# Sensor_Schematic.net
KiCad netlist of a schematic drawn in Altium Designer
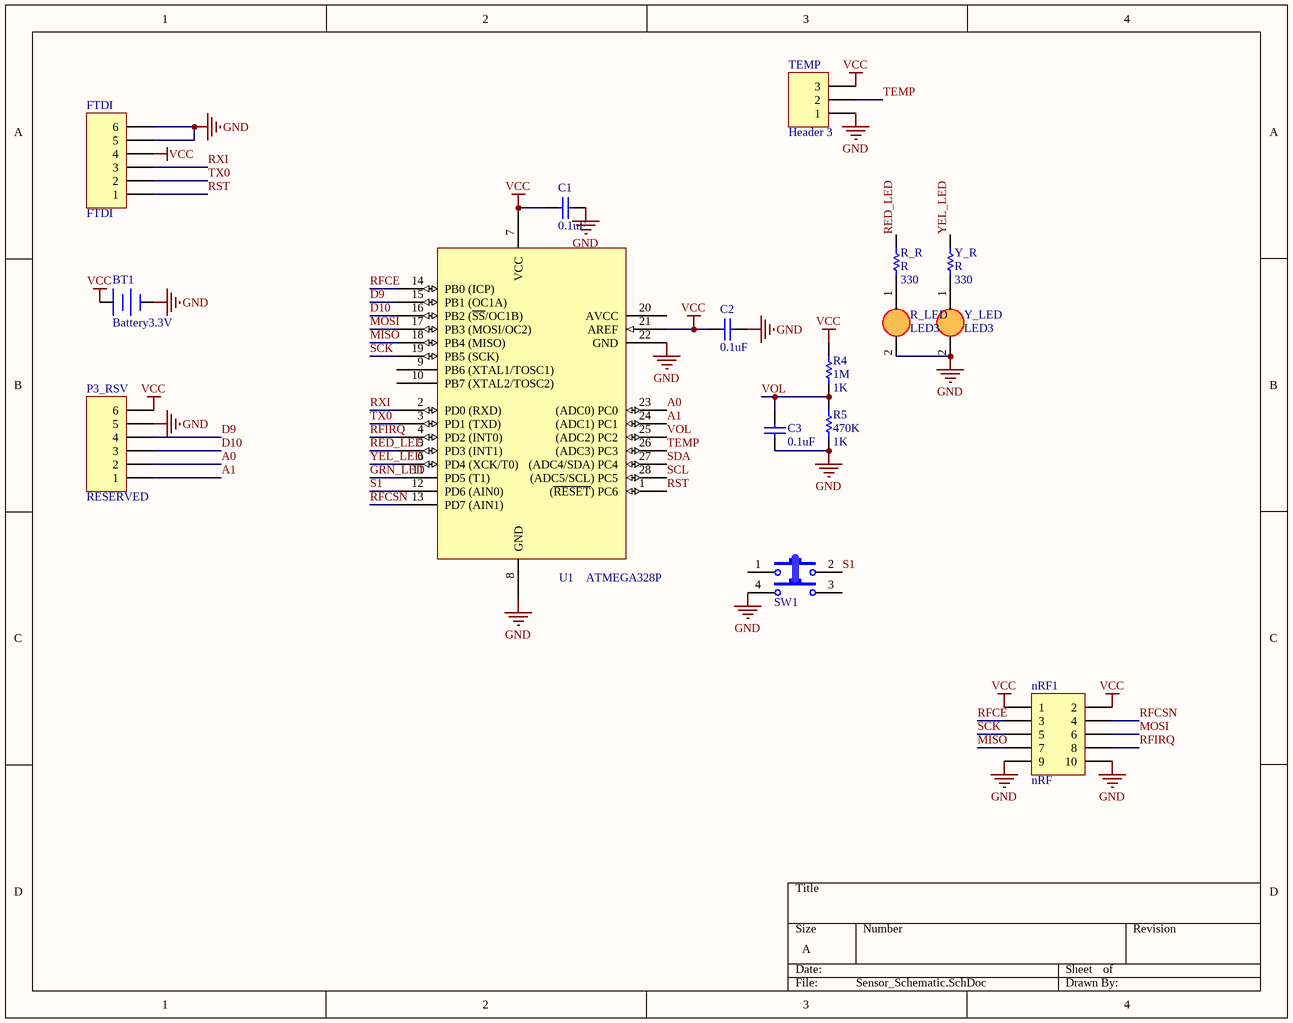
[diagram p0: Sensor_Schematic.SchDoc]

(export (version "E")
  (design (tool "Eeschema 10.0.6"))
  (components
    (comp (ref "BT1")
      (value "Battery3.3V")
      (footprint "CR2032 Holder")
      (description "Multicell Battery")
      (fields (field (name "PUBLISHER") "Altium Limited"))
      (libsource (lib "Arduino4Alitum_Library") (part "Battery3.3V"))
    )
    (comp (ref "C1")
      (value "0.1uF")
      (footprint "Tu-pico")
      (description "Capacitor")
      (fields (field (name "Comment") "Capacitor Ceramic") (field (name "PUBLISHER") "Altium Limited"))
      (libsource (lib "Arduino4Alitum_Library") (part "CapCeramic"))
    )
    (comp (ref "C2")
      (value "0.1uF")
      (footprint "Tu-pico")
      (description "Capacitor")
      (fields (field (name "Comment") "Capacitor Ceramic") (field (name "PUBLISHER") "Altium Limited"))
      (libsource (lib "Arduino4Alitum_Library") (part "CapCeramic"))
    )
    (comp (ref "C3")
      (value "0.1uF")
      (footprint "Tu-pico")
      (description "Capacitor")
      (fields (field (name "Comment") "Capacitor Ceramic") (field (name "PUBLISHER") "Altium Limited"))
      (libsource (lib "Arduino4Alitum_Library") (part "CapCeramic"))
    )
    (comp (ref "FTDI")
      (value "FTDI")
      (footprint "HDR1X6")
      (description "Header, 6-Pin")
      (fields (field (name "PUBLISHER") "Altium Limited"))
      (libsource (lib "Miscellaneous Connectors") (part "Header 6"))
    )
    (comp (ref "nRF1")
      (value "nRF")
      (footprint "HDR2X5")
      (description "Header, 5-Pin, Dual row")
      (fields (field (name "PUBLISHER") "Altium Limited"))
      (libsource (lib "Miscellaneous Connectors") (part "Header 5X2"))
    )
    (comp (ref "P3_RSV")
      (value "RESERVED")
      (footprint "HDR1X6")
      (description "Header, 6-Pin")
      (fields (field (name "PUBLISHER") "Altium Limited"))
      (libsource (lib "Miscellaneous Connectors") (part "Header 6"))
    )
    (comp (ref "R4")
      (value "1M")
      (footprint "AXIAL-0.3")
      (description "Resistor")
      (fields (field (name "ALTIUM_VALUE") "1K") (field (name "PUBLISHER") "Altium Limited"))
      (libsource (lib "Miscellaneous Devices") (part "Res1"))
    )
    (comp (ref "R5")
      (value "470K")
      (footprint "AXIAL-0.3")
      (description "Resistor")
      (fields (field (name "ALTIUM_VALUE") "1K") (field (name "PUBLISHER") "Altium Limited"))
      (libsource (lib "Miscellaneous Devices") (part "Res1"))
    )
    (comp (ref "R_LED")
      (value "LED3")
      (footprint "LED3mm")
      (description "LED 3mm")
      (libsource (lib "Arduino4Alitum_Library") (part "LED 3mm"))
    )
    (comp (ref "R_R")
      (value "R")
      (footprint "AXIAL-0.3")
      (description "Resistor")
      (fields (field (name "ALTIUM_VALUE") "330") (field (name "PUBLISHER") "Altium Limited"))
      (libsource (lib "Miscellaneous Devices") (part "Res1"))
    )
    (comp (ref "SW1")
      (value "SW-4P-B")
      (footprint "SW-4P-B")
      (description "Switch Big 4 Pin")
      (fields (field (name "PUBLISHER") "Altium Limited"))
      (libsource (lib "NBBLib 14-03-2012") (part "SW-4PIN-BIG"))
    )
    (comp (ref "TEMP")
      (value "Header 3")
      (footprint "HDR1X3")
      (description "Header, 3-Pin")
      (fields (field (name "PUBLISHER") "Altium Limited"))
      (libsource (lib "Miscellaneous Connectors") (part "Header 3"))
    )
    (comp (ref "U1")
      (value "ATMEGA328P")
      (footprint "AVR_DIP28P")
      (description "Atmel Microcontroller - Library created by carel..  <www.mpfreezone.com>")
      (libsource (lib "Arduino4Alitum_Library") (part "ATMEGA8_DIP28"))
    )
    (comp (ref "Y_LED")
      (value "LED3")
      (footprint "LED3mm")
      (description "LED 3mm")
      (libsource (lib "Arduino4Alitum_Library") (part "LED 3mm"))
    )
    (comp (ref "Y_R")
      (value "R")
      (footprint "AXIAL-0.3")
      (description "Resistor")
      (fields (field (name "ALTIUM_VALUE") "330") (field (name "PUBLISHER") "Altium Limited"))
      (libsource (lib "Miscellaneous Devices") (part "Res1"))
    )
  )
  (nets
    (net (code "1") (name "/A0") (class "Default")
      (node (ref "P3_RSV") (pin "2") (pinfunction "2_2") (pintype "passive"))
      (node (ref "U1") (pin "23") (pinfunction "(ADC0)_PC0_23") (pintype "bidirectional"))
    )
    (net (code "2") (name "/A1") (class "Default")
      (node (ref "P3_RSV") (pin "1") (pinfunction "1_1") (pintype "passive"))
      (node (ref "U1") (pin "24") (pinfunction "(ADC1)_PC1_24") (pintype "bidirectional"))
    )
    (net (code "3") (name "/D9") (class "Default")
      (node (ref "P3_RSV") (pin "4") (pinfunction "4_4") (pintype "passive"))
      (node (ref "U1") (pin "15") (pinfunction "PB1_(OC1A)_15") (pintype "bidirectional"))
    )
    (net (code "4") (name "/D10") (class "Default")
      (node (ref "P3_RSV") (pin "3") (pinfunction "3_3") (pintype "passive"))
      (node (ref "U1") (pin "16") (pinfunction "PB2_(~{SS}/OC1B)_16") (pintype "bidirectional"))
    )
    (net (code "5") (name "/GRN_LED") (class "Default")
      (node (ref "U1") (pin "11") (pinfunction "PD5_(T1)_11") (pintype "passive"))
    )
    (net (code "6") (name "/MISO") (class "Default")
      (node (ref "U1") (pin "18") (pinfunction "PB4_(MISO)_18") (pintype "bidirectional"))
      (node (ref "nRF1") (pin "7") (pinfunction "7_7") (pintype "passive"))
    )
    (net (code "7") (name "/MOSI") (class "Default")
      (node (ref "U1") (pin "17") (pinfunction "PB3_(MOSI/OC2)_17") (pintype "bidirectional"))
      (node (ref "nRF1") (pin "6") (pinfunction "6_6") (pintype "passive"))
    )
    (net (code "8") (name "/RED_LED") (class "Default")
      (node (ref "R_R") (pin "2") (pinfunction "2_2") (pintype "passive"))
      (node (ref "U1") (pin "5") (pinfunction "PD3_(INT1)_5") (pintype "bidirectional"))
    )
    (net (code "9") (name "/RFCE") (class "Default")
      (node (ref "U1") (pin "14") (pinfunction "PB0_(ICP)_14") (pintype "bidirectional"))
      (node (ref "nRF1") (pin "3") (pinfunction "3_3") (pintype "passive"))
    )
    (net (code "10") (name "/RFCSN") (class "Default")
      (node (ref "U1") (pin "13") (pinfunction "PD7_(AIN1)_13") (pintype "passive"))
      (node (ref "nRF1") (pin "4") (pinfunction "4_4") (pintype "passive"))
    )
    (net (code "11") (name "/RFIRQ") (class "Default")
      (node (ref "U1") (pin "4") (pinfunction "PD2_(INT0)_4") (pintype "bidirectional"))
      (node (ref "nRF1") (pin "8") (pinfunction "8_8") (pintype "passive"))
    )
    (net (code "12") (name "/RST") (class "Default")
      (node (ref "FTDI") (pin "1") (pinfunction "1_1") (pintype "passive"))
      (node (ref "U1") (pin "1") (pinfunction "(~{RESET})_PC6_1") (pintype "bidirectional"))
    )
    (net (code "13") (name "/RXI") (class "Default")
      (node (ref "FTDI") (pin "3") (pinfunction "3_3") (pintype "passive"))
      (node (ref "U1") (pin "2") (pinfunction "PD0_(RXD)_2") (pintype "bidirectional"))
    )
    (net (code "14") (name "/S1") (class "Default")
      (node (ref "SW1") (pin "2") (pinfunction "2_2") (pintype "passive"))
      (node (ref "U1") (pin "12") (pinfunction "PD6_(AIN0)_12") (pintype "passive"))
    )
    (net (code "15") (name "/SCK") (class "Default")
      (node (ref "U1") (pin "19") (pinfunction "PB5_(SCK)_19") (pintype "bidirectional"))
      (node (ref "nRF1") (pin "5") (pinfunction "5_5") (pintype "passive"))
    )
    (net (code "16") (name "/SCL") (class "Default")
      (node (ref "U1") (pin "28") (pinfunction "(ADC5/SCL)_PC5_28") (pintype "bidirectional"))
    )
    (net (code "17") (name "/SDA") (class "Default")
      (node (ref "U1") (pin "27") (pinfunction "(ADC4/SDA)_PC4_27") (pintype "bidirectional"))
    )
    (net (code "18") (name "/TEMP") (class "Default")
      (node (ref "TEMP") (pin "2") (pinfunction "2_2") (pintype "passive"))
      (node (ref "U1") (pin "26") (pinfunction "(ADC3)_PC3_26") (pintype "bidirectional"))
    )
    (net (code "19") (name "/TX0") (class "Default")
      (node (ref "FTDI") (pin "2") (pinfunction "2_2") (pintype "passive"))
      (node (ref "U1") (pin "3") (pinfunction "PD1_(TXD)_3") (pintype "bidirectional"))
    )
    (net (code "20") (name "/VOL") (class "Default")
      (node (ref "C3") (pin "2") (pinfunction "2_2") (pintype "passive"))
      (node (ref "R4") (pin "1") (pinfunction "1_1") (pintype "passive"))
      (node (ref "R5") (pin "2") (pinfunction "2_2") (pintype "passive"))
      (node (ref "U1") (pin "25") (pinfunction "(ADC2)_PC2_25") (pintype "bidirectional"))
    )
    (net (code "21") (name "/YEL_LED") (class "Default")
      (node (ref "U1") (pin "6") (pinfunction "PD4_(XCK/T0)_6") (pintype "bidirectional"))
      (node (ref "Y_R") (pin "2") (pinfunction "2_2") (pintype "passive"))
    )
    (net (code "22") (name "GND") (class "Default")
      (node (ref "BT1") (pin "2") (pinfunction "-_2") (pintype "passive"))
      (node (ref "C1") (pin "2") (pinfunction "2_2") (pintype "passive"))
      (node (ref "C2") (pin "2") (pinfunction "2_2") (pintype "passive"))
      (node (ref "C3") (pin "1") (pinfunction "1_1") (pintype "passive"))
      (node (ref "FTDI") (pin "5") (pinfunction "5_5") (pintype "passive"))
      (node (ref "FTDI") (pin "6") (pinfunction "6_6") (pintype "passive"))
      (node (ref "P3_RSV") (pin "5") (pinfunction "5_5") (pintype "passive"))
      (node (ref "R5") (pin "1") (pinfunction "1_1") (pintype "passive"))
      (node (ref "R_LED") (pin "2") (pinfunction "K_2") (pintype "passive"))
      (node (ref "SW1") (pin "4") (pinfunction "4_4") (pintype "passive"))
      (node (ref "TEMP") (pin "1") (pinfunction "1_1") (pintype "passive"))
      (node (ref "U1") (pin "22") (pinfunction "GND_22") (pintype "passive"))
      (node (ref "U1") (pin "8") (pinfunction "GND_8") (pintype "passive"))
      (node (ref "Y_LED") (pin "2") (pinfunction "K_2") (pintype "passive"))
      (node (ref "nRF1") (pin "10") (pinfunction "10_10") (pintype "passive"))
      (node (ref "nRF1") (pin "9") (pinfunction "9_9") (pintype "passive"))
    )
    (net (code "23") (name "Net-(R_LED-A)") (class "Default")
      (node (ref "R_LED") (pin "1") (pinfunction "A_1") (pintype "passive"))
      (node (ref "R_R") (pin "1") (pinfunction "1_1") (pintype "passive"))
    )
    (net (code "24") (name "Net-(Y_LED-A)") (class "Default")
      (node (ref "Y_LED") (pin "1") (pinfunction "A_1") (pintype "passive"))
      (node (ref "Y_R") (pin "1") (pinfunction "1_1") (pintype "passive"))
    )
    (net (code "25") (name "VCC") (class "Default")
      (node (ref "BT1") (pin "1") (pinfunction "+_1") (pintype "passive"))
      (node (ref "C1") (pin "1") (pinfunction "1_1") (pintype "passive"))
      (node (ref "C2") (pin "1") (pinfunction "1_1") (pintype "passive"))
      (node (ref "FTDI") (pin "4") (pinfunction "4_4") (pintype "passive"))
      (node (ref "P3_RSV") (pin "6") (pinfunction "6_6") (pintype "passive"))
      (node (ref "R4") (pin "2") (pinfunction "2_2") (pintype "passive"))
      (node (ref "TEMP") (pin "3") (pinfunction "3_3") (pintype "passive"))
      (node (ref "U1") (pin "21") (pinfunction "AREF_21") (pintype "input"))
      (node (ref "U1") (pin "7") (pinfunction "VCC_7") (pintype "passive"))
      (node (ref "nRF1") (pin "1") (pinfunction "1_1") (pintype "passive"))
      (node (ref "nRF1") (pin "2") (pinfunction "2_2") (pintype "passive"))
    )
    (net (code "26") (name "unconnected-(SW1-Pad1)") (class "Default")
      (node (ref "SW1") (pin "1") (pinfunction "1_1") (pintype "passive"))
    )
    (net (code "27") (name "unconnected-(SW1-Pad3)") (class "Default")
      (node (ref "SW1") (pin "3") (pinfunction "3_3") (pintype "passive"))
    )
    (net (code "28") (name "unconnected-(U1-AVCC-Pad20)") (class "Default")
      (node (ref "U1") (pin "20") (pinfunction "AVCC_20") (pintype "passive"))
    )
    (net (code "29") (name "unconnected-(U1-PB6_(XTAL1{slash}TOSC1)-Pad9)") (class "Default")
      (node (ref "U1") (pin "9") (pinfunction "PB6_(XTAL1/TOSC1)_9") (pintype "passive"))
    )
    (net (code "30") (name "unconnected-(U1-PB7_(XTAL2{slash}TOSC2)-Pad10)") (class "Default")
      (node (ref "U1") (pin "10") (pinfunction "PB7_(XTAL2/TOSC2)_10") (pintype "passive"))
    )
  )
)
